# A7_POWER_-.net
KiCad netlist of a schematic drawn in Altium Designer
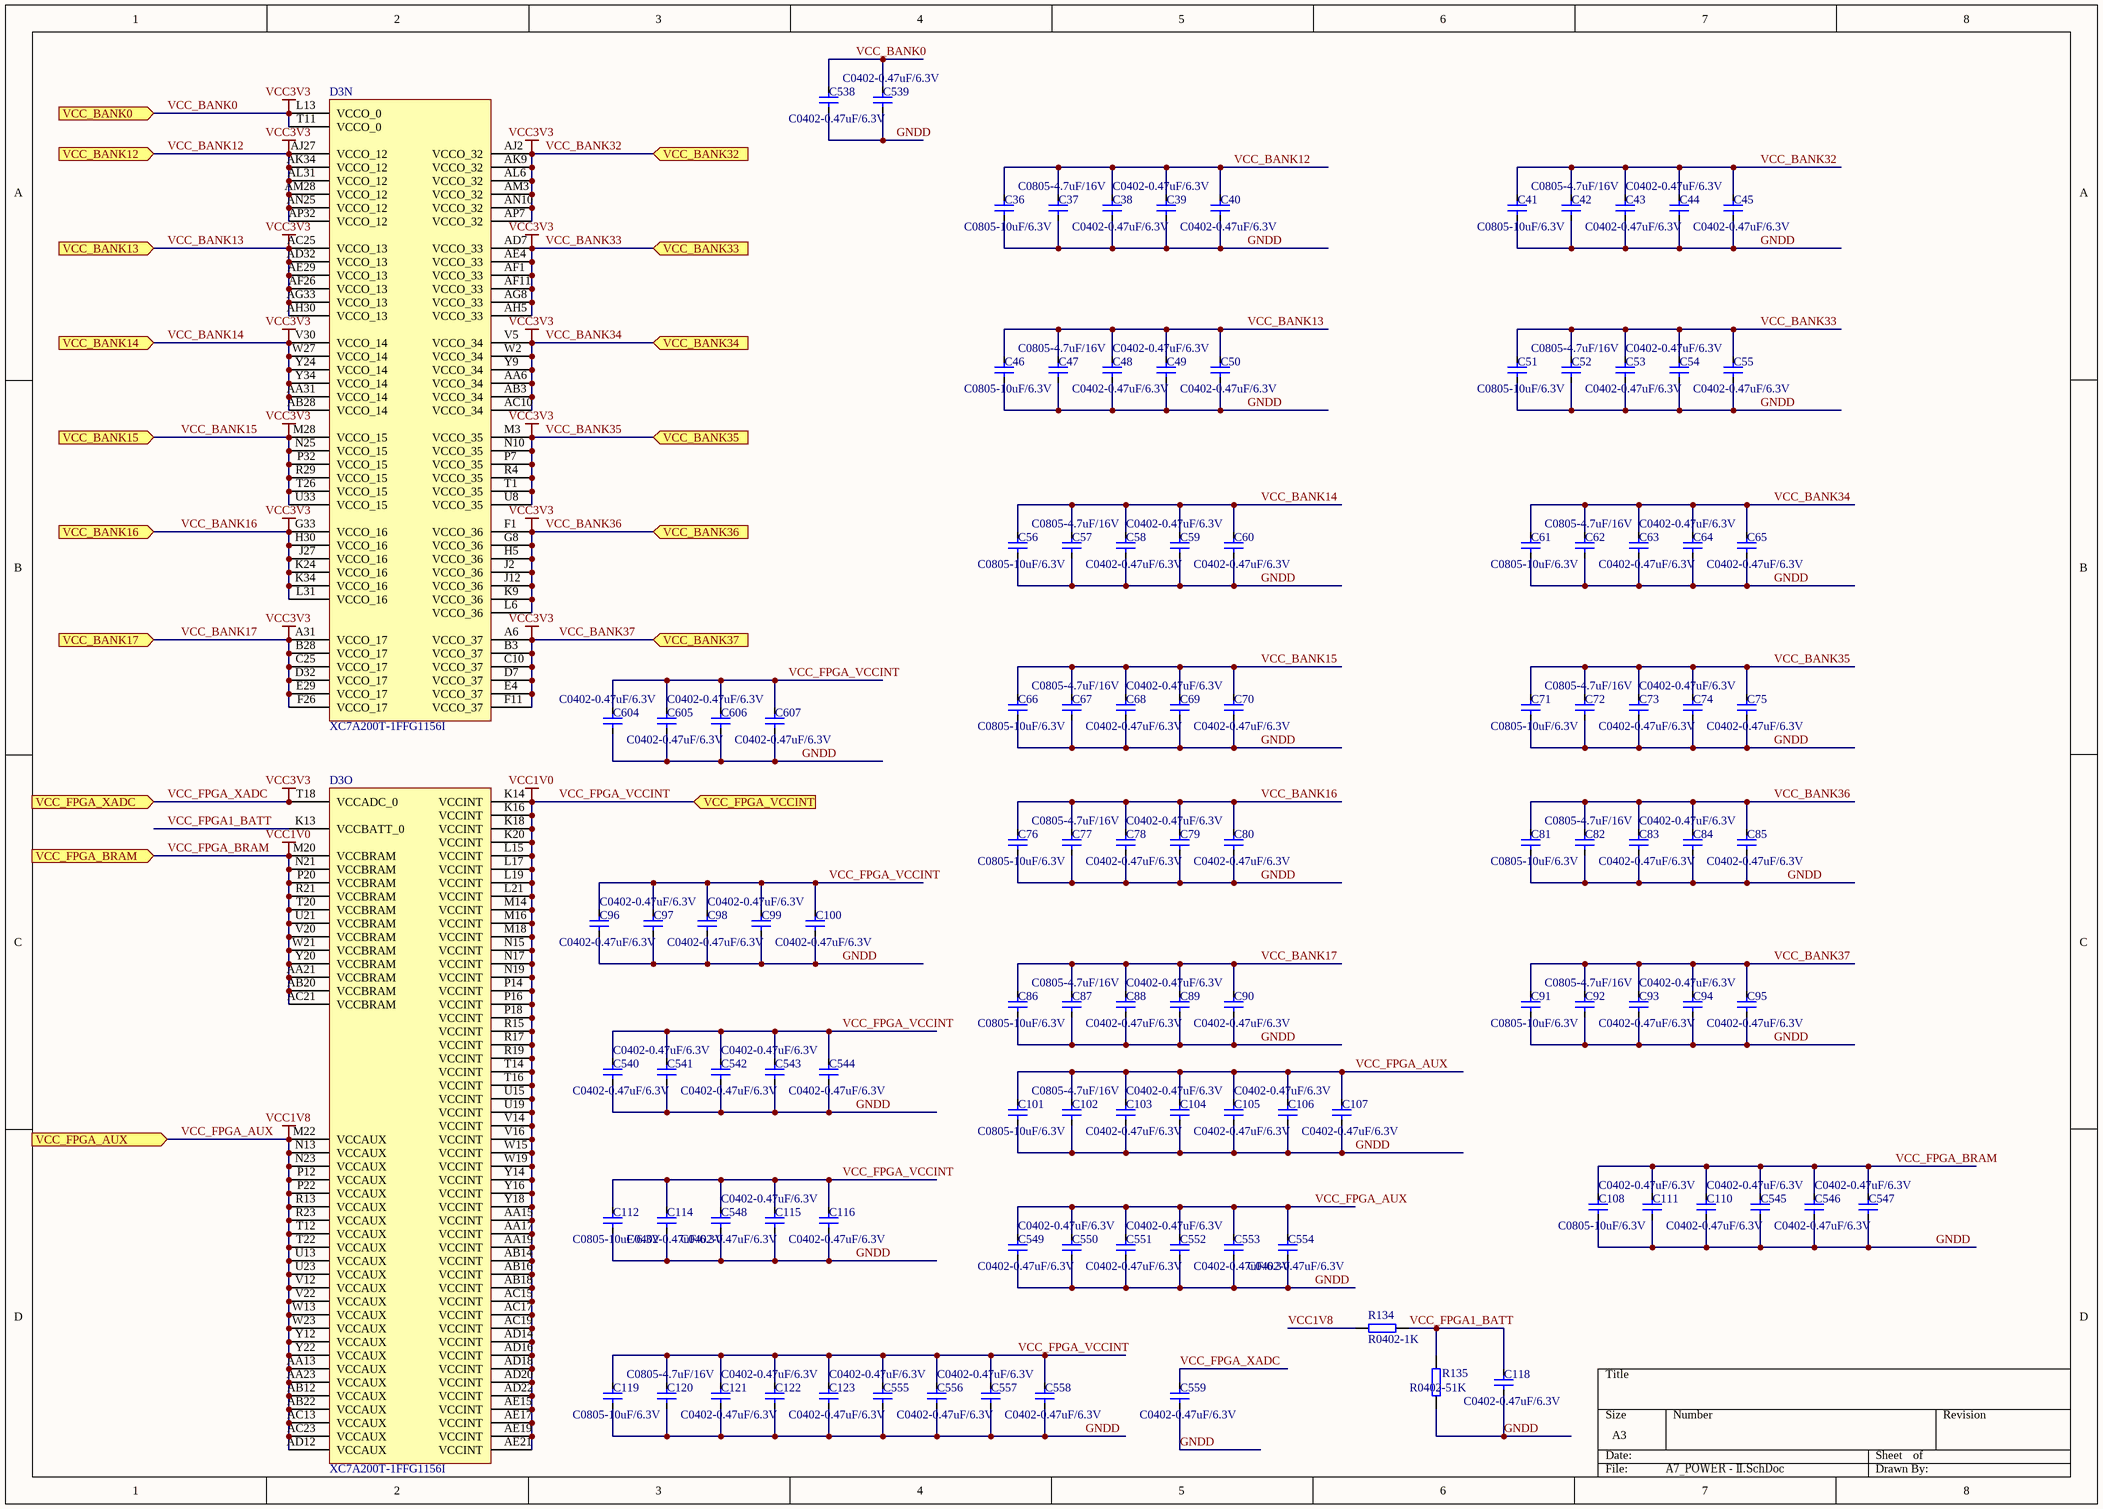
[diagram p0: A7_POWER - Ⅱ.SchDoc]

(export (version "E")
  (design (tool "Eeschema 10.0.6"))
  (components
    (comp (ref "C36")
      (value "C0805-10uF/6.3V")
      (footprint "C0805")
      (fields (field (name "SCHEMATIC_PART") "CAP"))
      (libsource (lib "Database_Libs1") (part "CAP"))
    )
    (comp (ref "C37")
      (value "C0805-4.7uF/16V")
      (footprint "C0805")
      (description "X7R")
      (fields (field (name "SCHEMATIC_PART") "CAP") (field (name "MANUFACTURER") "SAMSUNG"))
      (libsource (lib "Database_Libs1") (part "CAP"))
    )
    (comp (ref "C38")
      (value "C0402-0.47uF/6.3V")
      (footprint "C0402")
      (description "X7R")
      (fields (field (name "SCHEMATIC_PART") "CAP") (field (name "MANUFACTURER") "SAMSUNG"))
      (libsource (lib "Database_Libs1") (part "CAP"))
    )
    (comp (ref "C39")
      (value "C0402-0.47uF/6.3V")
      (footprint "C0402")
      (description "X7R")
      (fields (field (name "SCHEMATIC_PART") "CAP") (field (name "MANUFACTURER") "SAMSUNG"))
      (libsource (lib "Database_Libs1") (part "CAP"))
    )
    (comp (ref "C40")
      (value "C0402-0.47uF/6.3V")
      (footprint "C0402")
      (description "X7R")
      (fields (field (name "SCHEMATIC_PART") "CAP") (field (name "MANUFACTURER") "SAMSUNG"))
      (libsource (lib "Database_Libs1") (part "CAP"))
    )
    (comp (ref "C41")
      (value "C0805-10uF/6.3V")
      (footprint "C0805")
      (fields (field (name "SCHEMATIC_PART") "CAP"))
      (libsource (lib "Database_Libs1") (part "CAP"))
    )
    (comp (ref "C42")
      (value "C0805-4.7uF/16V")
      (footprint "C0805")
      (description "X7R")
      (fields (field (name "SCHEMATIC_PART") "CAP") (field (name "MANUFACTURER") "SAMSUNG"))
      (libsource (lib "Database_Libs1") (part "CAP"))
    )
    (comp (ref "C43")
      (value "C0402-0.47uF/6.3V")
      (footprint "C0402")
      (description "X7R")
      (fields (field (name "SCHEMATIC_PART") "CAP") (field (name "MANUFACTURER") "SAMSUNG"))
      (libsource (lib "Database_Libs1") (part "CAP"))
    )
    (comp (ref "C44")
      (value "C0402-0.47uF/6.3V")
      (footprint "C0402")
      (description "X7R")
      (fields (field (name "SCHEMATIC_PART") "CAP") (field (name "MANUFACTURER") "SAMSUNG"))
      (libsource (lib "Database_Libs1") (part "CAP"))
    )
    (comp (ref "C45")
      (value "C0402-0.47uF/6.3V")
      (footprint "C0402")
      (description "X7R")
      (fields (field (name "SCHEMATIC_PART") "CAP") (field (name "MANUFACTURER") "SAMSUNG"))
      (libsource (lib "Database_Libs1") (part "CAP"))
    )
    (comp (ref "C46")
      (value "C0805-10uF/6.3V")
      (footprint "C0805")
      (fields (field (name "SCHEMATIC_PART") "CAP"))
      (libsource (lib "Database_Libs1") (part "CAP"))
    )
    (comp (ref "C47")
      (value "C0805-4.7uF/16V")
      (footprint "C0805")
      (description "X7R")
      (fields (field (name "SCHEMATIC_PART") "CAP") (field (name "MANUFACTURER") "SAMSUNG"))
      (libsource (lib "Database_Libs1") (part "CAP"))
    )
    (comp (ref "C48")
      (value "C0402-0.47uF/6.3V")
      (footprint "C0402")
      (description "X7R")
      (fields (field (name "SCHEMATIC_PART") "CAP") (field (name "MANUFACTURER") "SAMSUNG"))
      (libsource (lib "Database_Libs1") (part "CAP"))
    )
    (comp (ref "C49")
      (value "C0402-0.47uF/6.3V")
      (footprint "C0402")
      (description "X7R")
      (fields (field (name "SCHEMATIC_PART") "CAP") (field (name "MANUFACTURER") "SAMSUNG"))
      (libsource (lib "Database_Libs1") (part "CAP"))
    )
    (comp (ref "C50")
      (value "C0402-0.47uF/6.3V")
      (footprint "C0402")
      (description "X7R")
      (fields (field (name "SCHEMATIC_PART") "CAP") (field (name "MANUFACTURER") "SAMSUNG"))
      (libsource (lib "Database_Libs1") (part "CAP"))
    )
    (comp (ref "C51")
      (value "C0805-10uF/6.3V")
      (footprint "C0805")
      (fields (field (name "SCHEMATIC_PART") "CAP"))
      (libsource (lib "Database_Libs1") (part "CAP"))
    )
    (comp (ref "C52")
      (value "C0805-4.7uF/16V")
      (footprint "C0805")
      (description "X7R")
      (fields (field (name "SCHEMATIC_PART") "CAP") (field (name "MANUFACTURER") "SAMSUNG"))
      (libsource (lib "Database_Libs1") (part "CAP"))
    )
    (comp (ref "C53")
      (value "C0402-0.47uF/6.3V")
      (footprint "C0402")
      (description "X7R")
      (fields (field (name "SCHEMATIC_PART") "CAP") (field (name "MANUFACTURER") "SAMSUNG"))
      (libsource (lib "Database_Libs1") (part "CAP"))
    )
    (comp (ref "C54")
      (value "C0402-0.47uF/6.3V")
      (footprint "C0402")
      (description "X7R")
      (fields (field (name "SCHEMATIC_PART") "CAP") (field (name "MANUFACTURER") "SAMSUNG"))
      (libsource (lib "Database_Libs1") (part "CAP"))
    )
    (comp (ref "C55")
      (value "C0402-0.47uF/6.3V")
      (footprint "C0402")
      (description "X7R")
      (fields (field (name "SCHEMATIC_PART") "CAP") (field (name "MANUFACTURER") "SAMSUNG"))
      (libsource (lib "Database_Libs1") (part "CAP"))
    )
    (comp (ref "C56")
      (value "C0805-10uF/6.3V")
      (footprint "C0805")
      (fields (field (name "SCHEMATIC_PART") "CAP"))
      (libsource (lib "Database_Libs1") (part "CAP"))
    )
    (comp (ref "C57")
      (value "C0805-4.7uF/16V")
      (footprint "C0805")
      (description "X7R")
      (fields (field (name "SCHEMATIC_PART") "CAP") (field (name "MANUFACTURER") "SAMSUNG"))
      (libsource (lib "Database_Libs1") (part "CAP"))
    )
    (comp (ref "C58")
      (value "C0402-0.47uF/6.3V")
      (footprint "C0402")
      (description "X7R")
      (fields (field (name "SCHEMATIC_PART") "CAP") (field (name "MANUFACTURER") "SAMSUNG"))
      (libsource (lib "Database_Libs1") (part "CAP"))
    )
    (comp (ref "C59")
      (value "C0402-0.47uF/6.3V")
      (footprint "C0402")
      (description "X7R")
      (fields (field (name "SCHEMATIC_PART") "CAP") (field (name "MANUFACTURER") "SAMSUNG"))
      (libsource (lib "Database_Libs1") (part "CAP"))
    )
    (comp (ref "C60")
      (value "C0402-0.47uF/6.3V")
      (footprint "C0402")
      (description "X7R")
      (fields (field (name "SCHEMATIC_PART") "CAP") (field (name "MANUFACTURER") "SAMSUNG"))
      (libsource (lib "Database_Libs1") (part "CAP"))
    )
    (comp (ref "C61")
      (value "C0805-10uF/6.3V")
      (footprint "C0805")
      (fields (field (name "SCHEMATIC_PART") "CAP"))
      (libsource (lib "Database_Libs1") (part "CAP"))
    )
    (comp (ref "C62")
      (value "C0805-4.7uF/16V")
      (footprint "C0805")
      (description "X7R")
      (fields (field (name "SCHEMATIC_PART") "CAP") (field (name "MANUFACTURER") "SAMSUNG"))
      (libsource (lib "Database_Libs1") (part "CAP"))
    )
    (comp (ref "C63")
      (value "C0402-0.47uF/6.3V")
      (footprint "C0402")
      (description "X7R")
      (fields (field (name "SCHEMATIC_PART") "CAP") (field (name "MANUFACTURER") "SAMSUNG"))
      (libsource (lib "Database_Libs1") (part "CAP"))
    )
    (comp (ref "C64")
      (value "C0402-0.47uF/6.3V")
      (footprint "C0402")
      (description "X7R")
      (fields (field (name "SCHEMATIC_PART") "CAP") (field (name "MANUFACTURER") "SAMSUNG"))
      (libsource (lib "Database_Libs1") (part "CAP"))
    )
    (comp (ref "C65")
      (value "C0402-0.47uF/6.3V")
      (footprint "C0402")
      (description "X7R")
      (fields (field (name "SCHEMATIC_PART") "CAP") (field (name "MANUFACTURER") "SAMSUNG"))
      (libsource (lib "Database_Libs1") (part "CAP"))
    )
    (comp (ref "C66")
      (value "C0805-10uF/6.3V")
      (footprint "C0805")
      (fields (field (name "SCHEMATIC_PART") "CAP"))
      (libsource (lib "Database_Libs1") (part "CAP"))
    )
    (comp (ref "C67")
      (value "C0805-4.7uF/16V")
      (footprint "C0805")
      (description "X7R")
      (fields (field (name "SCHEMATIC_PART") "CAP") (field (name "MANUFACTURER") "SAMSUNG"))
      (libsource (lib "Database_Libs1") (part "CAP"))
    )
    (comp (ref "C68")
      (value "C0402-0.47uF/6.3V")
      (footprint "C0402")
      (description "X7R")
      (fields (field (name "SCHEMATIC_PART") "CAP") (field (name "MANUFACTURER") "SAMSUNG"))
      (libsource (lib "Database_Libs1") (part "CAP"))
    )
    (comp (ref "C69")
      (value "C0402-0.47uF/6.3V")
      (footprint "C0402")
      (description "X7R")
      (fields (field (name "SCHEMATIC_PART") "CAP") (field (name "MANUFACTURER") "SAMSUNG"))
      (libsource (lib "Database_Libs1") (part "CAP"))
    )
    (comp (ref "C70")
      (value "C0402-0.47uF/6.3V")
      (footprint "C0402")
      (description "X7R")
      (fields (field (name "SCHEMATIC_PART") "CAP") (field (name "MANUFACTURER") "SAMSUNG"))
      (libsource (lib "Database_Libs1") (part "CAP"))
    )
    (comp (ref "C71")
      (value "C0805-10uF/6.3V")
      (footprint "C0805")
      (fields (field (name "SCHEMATIC_PART") "CAP"))
      (libsource (lib "Database_Libs1") (part "CAP"))
    )
    (comp (ref "C72")
      (value "C0805-4.7uF/16V")
      (footprint "C0805")
      (description "X7R")
      (fields (field (name "SCHEMATIC_PART") "CAP") (field (name "MANUFACTURER") "SAMSUNG"))
      (libsource (lib "Database_Libs1") (part "CAP"))
    )
    (comp (ref "C73")
      (value "C0402-0.47uF/6.3V")
      (footprint "C0402")
      (description "X7R")
      (fields (field (name "SCHEMATIC_PART") "CAP") (field (name "MANUFACTURER") "SAMSUNG"))
      (libsource (lib "Database_Libs1") (part "CAP"))
    )
    (comp (ref "C74")
      (value "C0402-0.47uF/6.3V")
      (footprint "C0402")
      (description "X7R")
      (fields (field (name "SCHEMATIC_PART") "CAP") (field (name "MANUFACTURER") "SAMSUNG"))
      (libsource (lib "Database_Libs1") (part "CAP"))
    )
    (comp (ref "C75")
      (value "C0402-0.47uF/6.3V")
      (footprint "C0402")
      (description "X7R")
      (fields (field (name "SCHEMATIC_PART") "CAP") (field (name "MANUFACTURER") "SAMSUNG"))
      (libsource (lib "Database_Libs1") (part "CAP"))
    )
    (comp (ref "C76")
      (value "C0805-10uF/6.3V")
      (footprint "C0805")
      (fields (field (name "SCHEMATIC_PART") "CAP"))
      (libsource (lib "Database_Libs1") (part "CAP"))
    )
    (comp (ref "C77")
      (value "C0805-4.7uF/16V")
      (footprint "C0805")
      (description "X7R")
      (fields (field (name "SCHEMATIC_PART") "CAP") (field (name "MANUFACTURER") "SAMSUNG"))
      (libsource (lib "Database_Libs1") (part "CAP"))
    )
    (comp (ref "C78")
      (value "C0402-0.47uF/6.3V")
      (footprint "C0402")
      (description "X7R")
      (fields (field (name "SCHEMATIC_PART") "CAP") (field (name "MANUFACTURER") "SAMSUNG"))
      (libsource (lib "Database_Libs1") (part "CAP"))
    )
    (comp (ref "C79")
      (value "C0402-0.47uF/6.3V")
      (footprint "C0402")
      (description "X7R")
      (fields (field (name "SCHEMATIC_PART") "CAP") (field (name "MANUFACTURER") "SAMSUNG"))
      (libsource (lib "Database_Libs1") (part "CAP"))
    )
    (comp (ref "C80")
      (value "C0402-0.47uF/6.3V")
      (footprint "C0402")
      (description "X7R")
      (fields (field (name "SCHEMATIC_PART") "CAP") (field (name "MANUFACTURER") "SAMSUNG"))
      (libsource (lib "Database_Libs1") (part "CAP"))
    )
    (comp (ref "C81")
      (value "C0805-10uF/6.3V")
      (footprint "C0805")
      (fields (field (name "SCHEMATIC_PART") "CAP"))
      (libsource (lib "Database_Libs1") (part "CAP"))
    )
    (comp (ref "C82")
      (value "C0805-4.7uF/16V")
      (footprint "C0805")
      (description "X7R")
      (fields (field (name "SCHEMATIC_PART") "CAP") (field (name "MANUFACTURER") "SAMSUNG"))
      (libsource (lib "Database_Libs1") (part "CAP"))
    )
    (comp (ref "C83")
      (value "C0402-0.47uF/6.3V")
      (footprint "C0402")
      (description "X7R")
      (fields (field (name "SCHEMATIC_PART") "CAP") (field (name "MANUFACTURER") "SAMSUNG"))
      (libsource (lib "Database_Libs1") (part "CAP"))
    )
    (comp (ref "C84")
      (value "C0402-0.47uF/6.3V")
      (footprint "C0402")
      (description "X7R")
      (fields (field (name "SCHEMATIC_PART") "CAP") (field (name "MANUFACTURER") "SAMSUNG"))
      (libsource (lib "Database_Libs1") (part "CAP"))
    )
    (comp (ref "C85")
      (value "C0402-0.47uF/6.3V")
      (footprint "C0402")
      (description "X7R")
      (fields (field (name "SCHEMATIC_PART") "CAP") (field (name "MANUFACTURER") "SAMSUNG"))
      (libsource (lib "Database_Libs1") (part "CAP"))
    )
    (comp (ref "C86")
      (value "C0805-10uF/6.3V")
      (footprint "C0805")
      (fields (field (name "SCHEMATIC_PART") "CAP"))
      (libsource (lib "Database_Libs1") (part "CAP"))
    )
    (comp (ref "C87")
      (value "C0805-4.7uF/16V")
      (footprint "C0805")
      (description "X7R")
      (fields (field (name "SCHEMATIC_PART") "CAP") (field (name "MANUFACTURER") "SAMSUNG"))
      (libsource (lib "Database_Libs1") (part "CAP"))
    )
    (comp (ref "C88")
      (value "C0402-0.47uF/6.3V")
      (footprint "C0402")
      (description "X7R")
      (fields (field (name "SCHEMATIC_PART") "CAP") (field (name "MANUFACTURER") "SAMSUNG"))
      (libsource (lib "Database_Libs1") (part "CAP"))
    )
    (comp (ref "C89")
      (value "C0402-0.47uF/6.3V")
      (footprint "C0402")
      (description "X7R")
      (fields (field (name "SCHEMATIC_PART") "CAP") (field (name "MANUFACTURER") "SAMSUNG"))
      (libsource (lib "Database_Libs1") (part "CAP"))
    )
    (comp (ref "C90")
      (value "C0402-0.47uF/6.3V")
      (footprint "C0402")
      (description "X7R")
      (fields (field (name "SCHEMATIC_PART") "CAP") (field (name "MANUFACTURER") "SAMSUNG"))
      (libsource (lib "Database_Libs1") (part "CAP"))
    )
    (comp (ref "C91")
      (value "C0805-10uF/6.3V")
      (footprint "C0805")
      (fields (field (name "SCHEMATIC_PART") "CAP"))
      (libsource (lib "Database_Libs1") (part "CAP"))
    )
    (comp (ref "C92")
      (value "C0805-4.7uF/16V")
      (footprint "C0805")
      (description "X7R")
      (fields (field (name "SCHEMATIC_PART") "CAP") (field (name "MANUFACTURER") "SAMSUNG"))
      (libsource (lib "Database_Libs1") (part "CAP"))
    )
    (comp (ref "C93")
      (value "C0402-0.47uF/6.3V")
      (footprint "C0402")
      (description "X7R")
      (fields (field (name "SCHEMATIC_PART") "CAP") (field (name "MANUFACTURER") "SAMSUNG"))
      (libsource (lib "Database_Libs1") (part "CAP"))
    )
    (comp (ref "C94")
      (value "C0402-0.47uF/6.3V")
      (footprint "C0402")
      (description "X7R")
      (fields (field (name "SCHEMATIC_PART") "CAP") (field (name "MANUFACTURER") "SAMSUNG"))
      (libsource (lib "Database_Libs1") (part "CAP"))
    )
    (comp (ref "C95")
      (value "C0402-0.47uF/6.3V")
      (footprint "C0402")
      (description "X7R")
      (fields (field (name "SCHEMATIC_PART") "CAP") (field (name "MANUFACTURER") "SAMSUNG"))
      (libsource (lib "Database_Libs1") (part "CAP"))
    )
    (comp (ref "C96")
      (value "C0402-0.47uF/6.3V")
      (footprint "C0402")
      (description "X7R")
      (fields (field (name "SCHEMATIC_PART") "CAP") (field (name "MANUFACTURER") "SAMSUNG"))
      (libsource (lib "Database_Libs1") (part "CAP"))
    )
    (comp (ref "C97")
      (value "C0402-0.47uF/6.3V")
      (footprint "C0402")
      (description "X7R")
      (fields (field (name "SCHEMATIC_PART") "CAP") (field (name "MANUFACTURER") "SAMSUNG"))
      (libsource (lib "Database_Libs1") (part "CAP"))
    )
    (comp (ref "C98")
      (value "C0402-0.47uF/6.3V")
      (footprint "C0402")
      (description "X7R")
      (fields (field (name "SCHEMATIC_PART") "CAP") (field (name "MANUFACTURER") "SAMSUNG"))
      (libsource (lib "Database_Libs1") (part "CAP"))
    )
    (comp (ref "C99")
      (value "C0402-0.47uF/6.3V")
      (footprint "C0402")
      (description "X7R")
      (fields (field (name "SCHEMATIC_PART") "CAP") (field (name "MANUFACTURER") "SAMSUNG"))
      (libsource (lib "Database_Libs1") (part "CAP"))
    )
    (comp (ref "C100")
      (value "C0402-0.47uF/6.3V")
      (footprint "C0402")
      (description "X7R")
      (fields (field (name "SCHEMATIC_PART") "CAP") (field (name "MANUFACTURER") "SAMSUNG"))
      (libsource (lib "Database_Libs1") (part "CAP"))
    )
    (comp (ref "C101")
      (value "C0805-10uF/6.3V")
      (footprint "C0805")
      (fields (field (name "SCHEMATIC_PART") "CAP"))
      (libsource (lib "Database_Libs1") (part "CAP"))
    )
    (comp (ref "C102")
      (value "C0805-4.7uF/16V")
      (footprint "C0805")
      (description "X7R")
      (fields (field (name "SCHEMATIC_PART") "CAP") (field (name "MANUFACTURER") "SAMSUNG"))
      (libsource (lib "Database_Libs1") (part "CAP"))
    )
    (comp (ref "C103")
      (value "C0402-0.47uF/6.3V")
      (footprint "C0402")
      (description "X7R")
      (fields (field (name "SCHEMATIC_PART") "CAP") (field (name "MANUFACTURER") "SAMSUNG"))
      (libsource (lib "Database_Libs1") (part "CAP"))
    )
    (comp (ref "C104")
      (value "C0402-0.47uF/6.3V")
      (footprint "C0402")
      (description "X7R")
      (fields (field (name "SCHEMATIC_PART") "CAP") (field (name "MANUFACTURER") "SAMSUNG"))
      (libsource (lib "Database_Libs1") (part "CAP"))
    )
    (comp (ref "C105")
      (value "C0402-0.47uF/6.3V")
      (footprint "C0402")
      (description "X7R")
      (fields (field (name "SCHEMATIC_PART") "CAP") (field (name "MANUFACTURER") "SAMSUNG"))
      (libsource (lib "Database_Libs1") (part "CAP"))
    )
    (comp (ref "C106")
      (value "C0402-0.47uF/6.3V")
      (footprint "C0402")
      (description "X7R")
      (fields (field (name "SCHEMATIC_PART") "CAP") (field (name "MANUFACTURER") "SAMSUNG"))
      (libsource (lib "Database_Libs1") (part "CAP"))
    )
    (comp (ref "C107")
      (value "C0402-0.47uF/6.3V")
      (footprint "C0402")
      (description "X7R")
      (fields (field (name "SCHEMATIC_PART") "CAP") (field (name "MANUFACTURER") "SAMSUNG"))
      (libsource (lib "Database_Libs1") (part "CAP"))
    )
    (comp (ref "C108")
      (value "C0805-10uF/6.3V")
      (footprint "C0805")
      (fields (field (name "SCHEMATIC_PART") "CAP"))
      (libsource (lib "Database_Libs1") (part "CAP"))
    )
    (comp (ref "C110")
      (value "C0402-0.47uF/6.3V")
      (footprint "C0402")
      (description "X7R")
      (fields (field (name "SCHEMATIC_PART") "CAP") (field (name "MANUFACTURER") "SAMSUNG"))
      (libsource (lib "Database_Libs1") (part "CAP"))
    )
    (comp (ref "C111")
      (value "C0402-0.47uF/6.3V")
      (footprint "C0402")
      (description "X7R")
      (fields (field (name "SCHEMATIC_PART") "CAP") (field (name "MANUFACTURER") "SAMSUNG"))
      (libsource (lib "Database_Libs1") (part "CAP"))
    )
    (comp (ref "C112")
      (value "C0805-10uF/6.3V")
      (footprint "C0805")
      (fields (field (name "SCHEMATIC_PART") "CAP"))
      (libsource (lib "Database_Libs1") (part "CAP"))
    )
    (comp (ref "C114")
      (value "C0402-0.47uF/6.3V")
      (footprint "C0402")
      (description "X7R")
      (fields (field (name "SCHEMATIC_PART") "CAP") (field (name "MANUFACTURER") "SAMSUNG"))
      (libsource (lib "Database_Libs1") (part "CAP"))
    )
    (comp (ref "C115")
      (value "C0402-0.47uF/6.3V")
      (footprint "C0402")
      (description "X7R")
      (fields (field (name "SCHEMATIC_PART") "CAP") (field (name "MANUFACTURER") "SAMSUNG"))
      (libsource (lib "Database_Libs1") (part "CAP"))
    )
    (comp (ref "C116")
      (value "C0402-0.47uF/6.3V")
      (footprint "C0402")
      (description "X7R")
      (fields (field (name "SCHEMATIC_PART") "CAP") (field (name "MANUFACTURER") "SAMSUNG"))
      (libsource (lib "Database_Libs1") (part "CAP"))
    )
    (comp (ref "C118")
      (value "C0402-0.47uF/6.3V")
      (footprint "C0402")
      (description "X7R")
      (fields (field (name "SCHEMATIC_PART") "CAP") (field (name "MANUFACTURER") "SAMSUNG"))
      (libsource (lib "Database_Libs1") (part "CAP"))
    )
    (comp (ref "C119")
      (value "C0805-10uF/6.3V")
      (footprint "C0805")
      (fields (field (name "SCHEMATIC_PART") "CAP"))
      (libsource (lib "Database_Libs1") (part "CAP"))
    )
    (comp (ref "C120")
      (value "C0805-4.7uF/16V")
      (footprint "C0805")
      (description "X7R")
      (fields (field (name "SCHEMATIC_PART") "CAP") (field (name "MANUFACTURER") "SAMSUNG"))
      (libsource (lib "Database_Libs1") (part "CAP"))
    )
    (comp (ref "C121")
      (value "C0402-0.47uF/6.3V")
      (footprint "C0402")
      (description "X7R")
      (fields (field (name "SCHEMATIC_PART") "CAP") (field (name "MANUFACTURER") "SAMSUNG"))
      (libsource (lib "Database_Libs1") (part "CAP"))
    )
    (comp (ref "C122")
      (value "C0402-0.47uF/6.3V")
      (footprint "C0402")
      (description "X7R")
      (fields (field (name "SCHEMATIC_PART") "CAP") (field (name "MANUFACTURER") "SAMSUNG"))
      (libsource (lib "Database_Libs1") (part "CAP"))
    )
    (comp (ref "C123")
      (value "C0402-0.47uF/6.3V")
      (footprint "C0402")
      (description "X7R")
      (fields (field (name "SCHEMATIC_PART") "CAP") (field (name "MANUFACTURER") "SAMSUNG"))
      (libsource (lib "Database_Libs1") (part "CAP"))
    )
    (comp (ref "C538")
      (value "C0402-0.47uF/6.3V")
      (footprint "C0402")
      (description "X7R")
      (fields (field (name "SCHEMATIC_PART") "CAP") (field (name "MANUFACTURER") "SAMSUNG"))
      (libsource (lib "Database_Libs1") (part "CAP"))
    )
    (comp (ref "C539")
      (value "C0402-0.47uF/6.3V")
      (footprint "C0402")
      (description "X7R")
      (fields (field (name "SCHEMATIC_PART") "CAP") (field (name "MANUFACTURER") "SAMSUNG"))
      (libsource (lib "Database_Libs1") (part "CAP"))
    )
    (comp (ref "C540")
      (value "C0402-0.47uF/6.3V")
      (footprint "C0402")
      (description "X7R")
      (fields (field (name "SCHEMATIC_PART") "CAP") (field (name "MANUFACTURER") "SAMSUNG"))
      (libsource (lib "Database_Libs1") (part "CAP"))
    )
    (comp (ref "C541")
      (value "C0402-0.47uF/6.3V")
      (footprint "C0402")
      (description "X7R")
      (fields (field (name "SCHEMATIC_PART") "CAP") (field (name "MANUFACTURER") "SAMSUNG"))
      (libsource (lib "Database_Libs1") (part "CAP"))
    )
    (comp (ref "C542")
      (value "C0402-0.47uF/6.3V")
      (footprint "C0402")
      (description "X7R")
      (fields (field (name "SCHEMATIC_PART") "CAP") (field (name "MANUFACTURER") "SAMSUNG"))
      (libsource (lib "Database_Libs1") (part "CAP"))
    )
    (comp (ref "C543")
      (value "C0402-0.47uF/6.3V")
      (footprint "C0402")
      (description "X7R")
      (fields (field (name "SCHEMATIC_PART") "CAP") (field (name "MANUFACTURER") "SAMSUNG"))
      (libsource (lib "Database_Libs1") (part "CAP"))
    )
    (comp (ref "C544")
      (value "C0402-0.47uF/6.3V")
      (footprint "C0402")
      (description "X7R")
      (fields (field (name "SCHEMATIC_PART") "CAP") (field (name "MANUFACTURER") "SAMSUNG"))
      (libsource (lib "Database_Libs1") (part "CAP"))
    )
    (comp (ref "C545")
      (value "C0402-0.47uF/6.3V")
      (footprint "C0402")
      (description "X7R")
      (fields (field (name "SCHEMATIC_PART") "CAP") (field (name "MANUFACTURER") "SAMSUNG"))
      (libsource (lib "Database_Libs1") (part "CAP"))
    )
    (comp (ref "C546")
      (value "C0402-0.47uF/6.3V")
      (footprint "C0402")
      (description "X7R")
      (fields (field (name "SCHEMATIC_PART") "CAP") (field (name "MANUFACTURER") "SAMSUNG"))
      (libsource (lib "Database_Libs1") (part "CAP"))
    )
    (comp (ref "C547")
      (value "C0402-0.47uF/6.3V")
      (footprint "C0402")
      (description "X7R")
      (fields (field (name "SCHEMATIC_PART") "CAP") (field (name "MANUFACTURER") "SAMSUNG"))
      (libsource (lib "Database_Libs1") (part "CAP"))
    )
    (comp (ref "C548")
      (value "C0402-0.47uF/6.3V")
      (footprint "C0402")
      (description "X7R")
      (fields (field (name "SCHEMATIC_PART") "CAP") (field (name "MANUFACTURER") "SAMSUNG"))
      (libsource (lib "Database_Libs1") (part "CAP"))
    )
    (comp (ref "C549")
      (value "C0402-0.47uF/6.3V")
      (footprint "C0402")
      (description "X7R")
      (fields (field (name "SCHEMATIC_PART") "CAP") (field (name "MANUFACTURER") "SAMSUNG"))
      (libsource (lib "Database_Libs1") (part "CAP"))
    )
    (comp (ref "C550")
      (value "C0402-0.47uF/6.3V")
      (footprint "C0402")
      (description "X7R")
      (fields (field (name "SCHEMATIC_PART") "CAP") (field (name "MANUFACTURER") "SAMSUNG"))
      (libsource (lib "Database_Libs1") (part "CAP"))
    )
    (comp (ref "C551")
      (value "C0402-0.47uF/6.3V")
      (footprint "C0402")
      (description "X7R")
      (fields (field (name "SCHEMATIC_PART") "CAP") (field (name "MANUFACTURER") "SAMSUNG"))
      (libsource (lib "Database_Libs1") (part "CAP"))
    )
    (comp (ref "C552")
      (value "C0402-0.47uF/6.3V")
      (footprint "C0402")
      (description "X7R")
      (fields (field (name "SCHEMATIC_PART") "CAP") (field (name "MANUFACTURER") "SAMSUNG"))
      (libsource (lib "Database_Libs1") (part "CAP"))
    )
    (comp (ref "C553")
      (value "C0402-0.47uF/6.3V")
      (footprint "C0402")
      (description "X7R")
      (fields (field (name "SCHEMATIC_PART") "CAP") (field (name "MANUFACTURER") "SAMSUNG"))
      (libsource (lib "Database_Libs1") (part "CAP"))
    )
    (comp (ref "C554")
      (value "C0402-0.47uF/6.3V")
      (footprint "C0402")
      (description "X7R")
      (fields (field (name "SCHEMATIC_PART") "CAP") (field (name "MANUFACTURER") "SAMSUNG"))
      (libsource (lib "Database_Libs1") (part "CAP"))
    )
    (comp (ref "C555")
      (value "C0402-0.47uF/6.3V")
      (footprint "C0402")
      (description "X7R")
      (fields (field (name "SCHEMATIC_PART") "CAP") (field (name "MANUFACTURER") "SAMSUNG"))
      (libsource (lib "Database_Libs1") (part "CAP"))
    )
    (comp (ref "C556")
      (value "C0402-0.47uF/6.3V")
      (footprint "C0402")
      (description "X7R")
      (fields (field (name "SCHEMATIC_PART") "CAP") (field (name "MANUFACTURER") "SAMSUNG"))
      (libsource (lib "Database_Libs1") (part "CAP"))
    )
    (comp (ref "C557")
      (value "C0402-0.47uF/6.3V")
      (footprint "C0402")
      (description "X7R")
      (fields (field (name "SCHEMATIC_PART") "CAP") (field (name "MANUFACTURER") "SAMSUNG"))
      (libsource (lib "Database_Libs1") (part "CAP"))
    )
    (comp (ref "C558")
      (value "C0402-0.47uF/6.3V")
      (footprint "C0402")
      (description "X7R")
      (fields (field (name "SCHEMATIC_PART") "CAP") (field (name "MANUFACTURER") "SAMSUNG"))
      (libsource (lib "Database_Libs1") (part "CAP"))
    )
    (comp (ref "C559")
      (value "C0402-0.47uF/6.3V")
      (footprint "C0402")
      (description "X7R")
      (fields (field (name "SCHEMATIC_PART") "CAP") (field (name "MANUFACTURER") "SAMSUNG"))
      (libsource (lib "Database_Libs1") (part "CAP"))
    )
    (comp (ref "C604")
      (value "C0402-0.47uF/6.3V")
      (footprint "C0402")
      (description "X7R")
      (fields (field (name "SCHEMATIC_PART") "CAP") (field (name "MANUFACTURER") "SAMSUNG"))
      (libsource (lib "Database_Libs1") (part "CAP"))
    )
    (comp (ref "C605")
      (value "C0402-0.47uF/6.3V")
      (footprint "C0402")
      (description "X7R")
      (fields (field (name "SCHEMATIC_PART") "CAP") (field (name "MANUFACTURER") "SAMSUNG"))
      (libsource (lib "Database_Libs1") (part "CAP"))
    )
    (comp (ref "C606")
      (value "C0402-0.47uF/6.3V")
      (footprint "C0402")
      (description "X7R")
      (fields (field (name "SCHEMATIC_PART") "CAP") (field (name "MANUFACTURER") "SAMSUNG"))
      (libsource (lib "Database_Libs1") (part "CAP"))
    )
    (comp (ref "C607")
      (value "C0402-0.47uF/6.3V")
      (footprint "C0402")
      (description "X7R")
      (fields (field (name "SCHEMATIC_PART") "CAP") (field (name "MANUFACTURER") "SAMSUNG"))
      (libsource (lib "Database_Libs1") (part "CAP"))
    )
    (comp (ref "D3")
      (value "XC7A200T-1FFG1156I")
      (footprint "FFG1156")
      (description "Artix-7 FPGA, 500 User I/Os, 16 GTP, 1156-Ball BGA, Speed Grade 1, Industrial Grade, Pb-Free")
      (fields (field (name "GENERIC PART NUMBER") "XC7A200T") (field (name "MANUFACTURER") "Xilinx"))
      (libsource (lib "Xilinx Artix-7") (part "XC7A200T-1FFG1156I"))
    )
    (comp (ref "R134")
      (value "R0402-1K")
      (footprint "R0402")
      (fields (field (name "SCHEMATIC_PART") "RES") (field (name "MANUFACTURER") "SAMSUNG"))
      (libsource (lib "Database_Libs1") (part "RES"))
    )
    (comp (ref "R135")
      (value "R0402-51K")
      (footprint "R0402")
      (fields (field (name "SCHEMATIC_PART") "RES") (field (name "MANUFACTURER") "SAMSUNG"))
      (libsource (lib "Database_Libs1") (part "RES"))
    )
  )
  (nets
    (net (code "1") (name "/GNDD") (class "Default")
      (node (ref "C100") (pin "2") (pinfunction "2_2") (pintype "passive"))
      (node (ref "C101") (pin "2") (pinfunction "2_2") (pintype "passive"))
      (node (ref "C102") (pin "2") (pinfunction "2_2") (pintype "passive"))
      (node (ref "C103") (pin "2") (pinfunction "2_2") (pintype "passive"))
      (node (ref "C104") (pin "2") (pinfunction "2_2") (pintype "passive"))
      (node (ref "C105") (pin "2") (pinfunction "2_2") (pintype "passive"))
      (node (ref "C106") (pin "2") (pinfunction "2_2") (pintype "passive"))
      (node (ref "C107") (pin "2") (pinfunction "2_2") (pintype "passive"))
      (node (ref "C108") (pin "2") (pinfunction "2_2") (pintype "passive"))
      (node (ref "C110") (pin "2") (pinfunction "2_2") (pintype "passive"))
      (node (ref "C111") (pin "2") (pinfunction "2_2") (pintype "passive"))
      (node (ref "C112") (pin "2") (pinfunction "2_2") (pintype "passive"))
      (node (ref "C114") (pin "2") (pinfunction "2_2") (pintype "passive"))
      (node (ref "C115") (pin "2") (pinfunction "2_2") (pintype "passive"))
      (node (ref "C116") (pin "2") (pinfunction "2_2") (pintype "passive"))
      (node (ref "C118") (pin "2") (pinfunction "2_2") (pintype "passive"))
      (node (ref "C119") (pin "2") (pinfunction "2_2") (pintype "passive"))
      (node (ref "C120") (pin "2") (pinfunction "2_2") (pintype "passive"))
      (node (ref "C121") (pin "2") (pinfunction "2_2") (pintype "passive"))
      (node (ref "C122") (pin "2") (pinfunction "2_2") (pintype "passive"))
      (node (ref "C123") (pin "2") (pinfunction "2_2") (pintype "passive"))
      (node (ref "C36") (pin "2") (pinfunction "2_2") (pintype "passive"))
      (node (ref "C37") (pin "2") (pinfunction "2_2") (pintype "passive"))
      (node (ref "C38") (pin "2") (pinfunction "2_2") (pintype "passive"))
      (node (ref "C39") (pin "2") (pinfunction "2_2") (pintype "passive"))
      (node (ref "C40") (pin "2") (pinfunction "2_2") (pintype "passive"))
      (node (ref "C41") (pin "2") (pinfunction "2_2") (pintype "passive"))
      (node (ref "C42") (pin "2") (pinfunction "2_2") (pintype "passive"))
      (node (ref "C43") (pin "2") (pinfunction "2_2") (pintype "passive"))
      (node (ref "C44") (pin "2") (pinfunction "2_2") (pintype "passive"))
      (node (ref "C45") (pin "2") (pinfunction "2_2") (pintype "passive"))
      (node (ref "C46") (pin "2") (pinfunction "2_2") (pintype "passive"))
      (node (ref "C47") (pin "2") (pinfunction "2_2") (pintype "passive"))
      (node (ref "C48") (pin "2") (pinfunction "2_2") (pintype "passive"))
      (node (ref "C49") (pin "2") (pinfunction "2_2") (pintype "passive"))
      (node (ref "C50") (pin "2") (pinfunction "2_2") (pintype "passive"))
      (node (ref "C51") (pin "2") (pinfunction "2_2") (pintype "passive"))
      (node (ref "C52") (pin "2") (pinfunction "2_2") (pintype "passive"))
      (node (ref "C53") (pin "2") (pinfunction "2_2") (pintype "passive"))
      (node (ref "C538") (pin "2") (pinfunction "2_2") (pintype "passive"))
      (node (ref "C539") (pin "2") (pinfunction "2_2") (pintype "passive"))
      (node (ref "C54") (pin "2") (pinfunction "2_2") (pintype "passive"))
      (node (ref "C540") (pin "2") (pinfunction "2_2") (pintype "passive"))
      (node (ref "C541") (pin "2") (pinfunction "2_2") (pintype "passive"))
      (node (ref "C542") (pin "2") (pinfunction "2_2") (pintype "passive"))
      (node (ref "C543") (pin "2") (pinfunction "2_2") (pintype "passive"))
      (node (ref "C544") (pin "2") (pinfunction "2_2") (pintype "passive"))
      (node (ref "C545") (pin "2") (pinfunction "2_2") (pintype "passive"))
      (node (ref "C546") (pin "2") (pinfunction "2_2") (pintype "passive"))
      (node (ref "C547") (pin "2") (pinfunction "2_2") (pintype "passive"))
      (node (ref "C548") (pin "2") (pinfunction "2_2") (pintype "passive"))
      (node (ref "C549") (pin "2") (pinfunction "2_2") (pintype "passive"))
      (node (ref "C55") (pin "2") (pinfunction "2_2") (pintype "passive"))
      (node (ref "C550") (pin "2") (pinfunction "2_2") (pintype "passive"))
      (node (ref "C551") (pin "2") (pinfunction "2_2") (pintype "passive"))
      (node (ref "C552") (pin "2") (pinfunction "2_2") (pintype "passive"))
      (node (ref "C553") (pin "2") (pinfunction "2_2") (pintype "passive"))
      (node (ref "C554") (pin "2") (pinfunction "2_2") (pintype "passive"))
      (node (ref "C555") (pin "2") (pinfunction "2_2") (pintype "passive"))
      (node (ref "C556") (pin "2") (pinfunction "2_2") (pintype "passive"))
      (node (ref "C557") (pin "2") (pinfunction "2_2") (pintype "passive"))
      (node (ref "C558") (pin "2") (pinfunction "2_2") (pintype "passive"))
      (node (ref "C559") (pin "2") (pinfunction "2_2") (pintype "passive"))
      (node (ref "C56") (pin "2") (pinfunction "2_2") (pintype "passive"))
      (node (ref "C57") (pin "2") (pinfunction "2_2") (pintype "passive"))
      (node (ref "C58") (pin "2") (pinfunction "2_2") (pintype "passive"))
      (node (ref "C59") (pin "2") (pinfunction "2_2") (pintype "passive"))
      (node (ref "C60") (pin "2") (pinfunction "2_2") (pintype "passive"))
      (node (ref "C604") (pin "2") (pinfunction "2_2") (pintype "passive"))
      (node (ref "C605") (pin "2") (pinfunction "2_2") (pintype "passive"))
      (node (ref "C606") (pin "2") (pinfunction "2_2") (pintype "passive"))
      (node (ref "C607") (pin "2") (pinfunction "2_2") (pintype "passive"))
      (node (ref "C61") (pin "2") (pinfunction "2_2") (pintype "passive"))
      (node (ref "C62") (pin "2") (pinfunction "2_2") (pintype "passive"))
      (node (ref "C63") (pin "2") (pinfunction "2_2") (pintype "passive"))
      (node (ref "C64") (pin "2") (pinfunction "2_2") (pintype "passive"))
      (node (ref "C65") (pin "2") (pinfunction "2_2") (pintype "passive"))
      (node (ref "C66") (pin "2") (pinfunction "2_2") (pintype "passive"))
      (node (ref "C67") (pin "2") (pinfunction "2_2") (pintype "passive"))
      (node (ref "C68") (pin "2") (pinfunction "2_2") (pintype "passive"))
      (node (ref "C69") (pin "2") (pinfunction "2_2") (pintype "passive"))
      (node (ref "C70") (pin "2") (pinfunction "2_2") (pintype "passive"))
      (node (ref "C71") (pin "2") (pinfunction "2_2") (pintype "passive"))
      (node (ref "C72") (pin "2") (pinfunction "2_2") (pintype "passive"))
      (node (ref "C73") (pin "2") (pinfunction "2_2") (pintype "passive"))
      (node (ref "C74") (pin "2") (pinfunction "2_2") (pintype "passive"))
      (node (ref "C75") (pin "2") (pinfunction "2_2") (pintype "passive"))
      (node (ref "C76") (pin "2") (pinfunction "2_2") (pintype "passive"))
      (node (ref "C77") (pin "2") (pinfunction "2_2") (pintype "passive"))
      (node (ref "C78") (pin "2") (pinfunction "2_2") (pintype "passive"))
      (node (ref "C79") (pin "2") (pinfunction "2_2") (pintype "passive"))
      (node (ref "C80") (pin "2") (pinfunction "2_2") (pintype "passive"))
      (node (ref "C81") (pin "2") (pinfunction "2_2") (pintype "passive"))
      (node (ref "C82") (pin "2") (pinfunction "2_2") (pintype "passive"))
      (node (ref "C83") (pin "2") (pinfunction "2_2") (pintype "passive"))
      (node (ref "C84") (pin "2") (pinfunction "2_2") (pintype "passive"))
      (node (ref "C85") (pin "2") (pinfunction "2_2") (pintype "passive"))
      (node (ref "C86") (pin "2") (pinfunction "2_2") (pintype "passive"))
      (node (ref "C87") (pin "2") (pinfunction "2_2") (pintype "passive"))
      (node (ref "C88") (pin "2") (pinfunction "2_2") (pintype "passive"))
      (node (ref "C89") (pin "2") (pinfunction "2_2") (pintype "passive"))
      (node (ref "C90") (pin "2") (pinfunction "2_2") (pintype "passive"))
      (node (ref "C91") (pin "2") (pinfunction "2_2") (pintype "passive"))
      (node (ref "C92") (pin "2") (pinfunction "2_2") (pintype "passive"))
      (node (ref "C93") (pin "2") (pinfunction "2_2") (pintype "passive"))
      (node (ref "C94") (pin "2") (pinfunction "2_2") (pintype "passive"))
      (node (ref "C95") (pin "2") (pinfunction "2_2") (pintype "passive"))
      (node (ref "C96") (pin "2") (pinfunction "2_2") (pintype "passive"))
      (node (ref "C97") (pin "2") (pinfunction "2_2") (pintype "passive"))
      (node (ref "C98") (pin "2") (pinfunction "2_2") (pintype "passive"))
      (node (ref "C99") (pin "2") (pinfunction "2_2") (pintype "passive"))
      (node (ref "R135") (pin "1") (pintype "passive"))
    )
    (net (code "2") (name "/VCC_FPGA1_BATT") (class "Default")
      (node (ref "C118") (pin "1") (pinfunction "1_1") (pintype "passive"))
      (node (ref "D3") (pin "K13") (pinfunction "VCCBATT_0_K13") (pintype "power_in"))
      (node (ref "R134") (pin "1") (pintype "passive"))
      (node (ref "R135") (pin "2") (pintype "passive"))
    )
    (net (code "3") (name "VCC1V0") (class "Default")
      (node (ref "C100") (pin "1") (pinfunction "1_1") (pintype "passive"))
      (node (ref "C108") (pin "1") (pinfunction "1_1") (pintype "passive"))
      (node (ref "C110") (pin "1") (pinfunction "1_1") (pintype "passive"))
      (node (ref "C111") (pin "1") (pinfunction "1_1") (pintype "passive"))
      (node (ref "C112") (pin "1") (pinfunction "1_1") (pintype "passive"))
      (node (ref "C114") (pin "1") (pinfunction "1_1") (pintype "passive"))
      (node (ref "C115") (pin "1") (pinfunction "1_1") (pintype "passive"))
      (node (ref "C116") (pin "1") (pinfunction "1_1") (pintype "passive"))
      (node (ref "C119") (pin "1") (pinfunction "1_1") (pintype "passive"))
      (node (ref "C120") (pin "1") (pinfunction "1_1") (pintype "passive"))
      (node (ref "C121") (pin "1") (pinfunction "1_1") (pintype "passive"))
      (node (ref "C122") (pin "1") (pinfunction "1_1") (pintype "passive"))
      (node (ref "C123") (pin "1") (pinfunction "1_1") (pintype "passive"))
      (node (ref "C540") (pin "1") (pinfunction "1_1") (pintype "passive"))
      (node (ref "C541") (pin "1") (pinfunction "1_1") (pintype "passive"))
      (node (ref "C542") (pin "1") (pinfunction "1_1") (pintype "passive"))
      (node (ref "C543") (pin "1") (pinfunction "1_1") (pintype "passive"))
      (node (ref "C544") (pin "1") (pinfunction "1_1") (pintype "passive"))
      (node (ref "C545") (pin "1") (pinfunction "1_1") (pintype "passive"))
      (node (ref "C546") (pin "1") (pinfunction "1_1") (pintype "passive"))
      (node (ref "C547") (pin "1") (pinfunction "1_1") (pintype "passive"))
      (node (ref "C548") (pin "1") (pinfunction "1_1") (pintype "passive"))
      (node (ref "C555") (pin "1") (pinfunction "1_1") (pintype "passive"))
      (node (ref "C556") (pin "1") (pinfunction "1_1") (pintype "passive"))
      (node (ref "C557") (pin "1") (pinfunction "1_1") (pintype "passive"))
      (node (ref "C558") (pin "1") (pinfunction "1_1") (pintype "passive"))
      (node (ref "C604") (pin "1") (pinfunction "1_1") (pintype "passive"))
      (node (ref "C605") (pin "1") (pinfunction "1_1") (pintype "passive"))
      (node (ref "C606") (pin "1") (pinfunction "1_1") (pintype "passive"))
      (node (ref "C607") (pin "1") (pinfunction "1_1") (pintype "passive"))
      (node (ref "C96") (pin "1") (pinfunction "1_1") (pintype "passive"))
      (node (ref "C97") (pin "1") (pinfunction "1_1") (pintype "passive"))
      (node (ref "C98") (pin "1") (pinfunction "1_1") (pintype "passive"))
      (node (ref "C99") (pin "1") (pinfunction "1_1") (pintype "passive"))
      (node (ref "D3") (pin "AA15") (pinfunction "VCCINT_AA15") (pintype "power_in"))
      (node (ref "D3") (pin "AA17") (pinfunction "VCCINT_AA17") (pintype "power_in"))
      (node (ref "D3") (pin "AA19") (pinfunction "VCCINT_AA19") (pintype "power_in"))
      (node (ref "D3") (pin "AA21") (pinfunction "VCCBRAM_AA21") (pintype "power_in"))
      (node (ref "D3") (pin "AB14") (pinfunction "VCCINT_AB14") (pintype "power_in"))
      (node (ref "D3") (pin "AB16") (pinfunction "VCCINT_AB16") (pintype "power_in"))
      (node (ref "D3") (pin "AB18") (pinfunction "VCCINT_AB18") (pintype "power_in"))
      (node (ref "D3") (pin "AB20") (pinfunction "VCCBRAM_AB20") (pintype "power_in"))
      (node (ref "D3") (pin "AC15") (pinfunction "VCCINT_AC15") (pintype "power_in"))
      (node (ref "D3") (pin "AC17") (pinfunction "VCCINT_AC17") (pintype "power_in"))
      (node (ref "D3") (pin "AC19") (pinfunction "VCCINT_AC19") (pintype "power_in"))
      (node (ref "D3") (pin "AC21") (pinfunction "VCCBRAM_AC21") (pintype "power_in"))
      (node (ref "D3") (pin "AD14") (pinfunction "VCCINT_AD14") (pintype "power_in"))
      (node (ref "D3") (pin "AD16") (pinfunction "VCCINT_AD16") (pintype "power_in"))
      (node (ref "D3") (pin "AD18") (pinfunction "VCCINT_AD18") (pintype "power_in"))
      (node (ref "D3") (pin "AD20") (pinfunction "VCCINT_AD20") (pintype "power_in"))
      (node (ref "D3") (pin "AD22") (pinfunction "VCCINT_AD22") (pintype "power_in"))
      (node (ref "D3") (pin "AE15") (pinfunction "VCCINT_AE15") (pintype "power_in"))
      (node (ref "D3") (pin "AE17") (pinfunction "VCCINT_AE17") (pintype "power_in"))
      (node (ref "D3") (pin "AE19") (pinfunction "VCCINT_AE19") (pintype "power_in"))
      (node (ref "D3") (pin "AE21") (pinfunction "VCCINT_AE21") (pintype "power_in"))
      (node (ref "D3") (pin "K14") (pinfunction "VCCINT_K14") (pintype "power_in"))
      (node (ref "D3") (pin "K16") (pinfunction "VCCINT_K16") (pintype "power_in"))
      (node (ref "D3") (pin "K18") (pinfunction "VCCINT_K18") (pintype "power_in"))
      (node (ref "D3") (pin "K20") (pinfunction "VCCINT_K20") (pintype "power_in"))
      (node (ref "D3") (pin "L15") (pinfunction "VCCINT_L15") (pintype "power_in"))
      (node (ref "D3") (pin "L17") (pinfunction "VCCINT_L17") (pintype "power_in"))
      (node (ref "D3") (pin "L19") (pinfunction "VCCINT_L19") (pintype "power_in"))
      (node (ref "D3") (pin "L21") (pinfunction "VCCINT_L21") (pintype "power_in"))
      (node (ref "D3") (pin "M14") (pinfunction "VCCINT_M14") (pintype "power_in"))
      (node (ref "D3") (pin "M16") (pinfunction "VCCINT_M16") (pintype "power_in"))
      (node (ref "D3") (pin "M18") (pinfunction "VCCINT_M18") (pintype "power_in"))
      (node (ref "D3") (pin "M20") (pinfunction "VCCBRAM_M20") (pintype "power_in"))
      (node (ref "D3") (pin "N15") (pinfunction "VCCINT_N15") (pintype "power_in"))
      (node (ref "D3") (pin "N17") (pinfunction "VCCINT_N17") (pintype "power_in"))
      (node (ref "D3") (pin "N19") (pinfunction "VCCINT_N19") (pintype "power_in"))
      (node (ref "D3") (pin "N21") (pinfunction "VCCBRAM_N21") (pintype "power_in"))
      (node (ref "D3") (pin "P14") (pinfunction "VCCINT_P14") (pintype "power_in"))
      (node (ref "D3") (pin "P16") (pinfunction "VCCINT_P16") (pintype "power_in"))
      (node (ref "D3") (pin "P18") (pinfunction "VCCINT_P18") (pintype "power_in"))
      (node (ref "D3") (pin "P20") (pinfunction "VCCBRAM_P20") (pintype "power_in"))
      (node (ref "D3") (pin "R15") (pinfunction "VCCINT_R15") (pintype "power_in"))
      (node (ref "D3") (pin "R17") (pinfunction "VCCINT_R17") (pintype "power_in"))
      (node (ref "D3") (pin "R19") (pinfunction "VCCINT_R19") (pintype "power_in"))
      (node (ref "D3") (pin "R21") (pinfunction "VCCBRAM_R21") (pintype "power_in"))
      (node (ref "D3") (pin "T14") (pinfunction "VCCINT_T14") (pintype "power_in"))
      (node (ref "D3") (pin "T16") (pinfunction "VCCINT_T16") (pintype "power_in"))
      (node (ref "D3") (pin "T20") (pinfunction "VCCBRAM_T20") (pintype "power_in"))
      (node (ref "D3") (pin "U15") (pinfunction "VCCINT_U15") (pintype "power_in"))
      (node (ref "D3") (pin "U19") (pinfunction "VCCINT_U19") (pintype "power_in"))
      (node (ref "D3") (pin "U21") (pinfunction "VCCBRAM_U21") (pintype "power_in"))
      (node (ref "D3") (pin "V14") (pinfunction "VCCINT_V14") (pintype "power_in"))
      (node (ref "D3") (pin "V16") (pinfunction "VCCINT_V16") (pintype "power_in"))
      (node (ref "D3") (pin "V20") (pinfunction "VCCBRAM_V20") (pintype "power_in"))
      (node (ref "D3") (pin "W15") (pinfunction "VCCINT_W15") (pintype "power_in"))
      (node (ref "D3") (pin "W19") (pinfunction "VCCINT_W19") (pintype "power_in"))
      (node (ref "D3") (pin "W21") (pinfunction "VCCBRAM_W21") (pintype "power_in"))
      (node (ref "D3") (pin "Y14") (pinfunction "VCCINT_Y14") (pintype "power_in"))
      (node (ref "D3") (pin "Y16") (pinfunction "VCCINT_Y16") (pintype "power_in"))
      (node (ref "D3") (pin "Y18") (pinfunction "VCCINT_Y18") (pintype "power_in"))
      (node (ref "D3") (pin "Y20") (pinfunction "VCCBRAM_Y20") (pintype "power_in"))
    )
    (net (code "4") (name "VCC1V8") (class "Default")
      (node (ref "C101") (pin "1") (pinfunction "1_1") (pintype "passive"))
      (node (ref "C102") (pin "1") (pinfunction "1_1") (pintype "passive"))
      (node (ref "C103") (pin "1") (pinfunction "1_1") (pintype "passive"))
      (node (ref "C104") (pin "1") (pinfunction "1_1") (pintype "passive"))
      (node (ref "C105") (pin "1") (pinfunction "1_1") (pintype "passive"))
      (node (ref "C106") (pin "1") (pinfunction "1_1") (pintype "passive"))
      (node (ref "C107") (pin "1") (pinfunction "1_1") (pintype "passive"))
      (node (ref "C549") (pin "1") (pinfunction "1_1") (pintype "passive"))
      (node (ref "C550") (pin "1") (pinfunction "1_1") (pintype "passive"))
      (node (ref "C551") (pin "1") (pinfunction "1_1") (pintype "passive"))
      (node (ref "C552") (pin "1") (pinfunction "1_1") (pintype "passive"))
      (node (ref "C553") (pin "1") (pinfunction "1_1") (pintype "passive"))
      (node (ref "C554") (pin "1") (pinfunction "1_1") (pintype "passive"))
      (node (ref "D3") (pin "AA13") (pinfunction "VCCAUX_AA13") (pintype "power_in"))
      (node (ref "D3") (pin "AA23") (pinfunction "VCCAUX_AA23") (pintype "power_in"))
      (node (ref "D3") (pin "AB12") (pinfunction "VCCAUX_AB12") (pintype "power_in"))
      (node (ref "D3") (pin "AB22") (pinfunction "VCCAUX_AB22") (pintype "power_in"))
      (node (ref "D3") (pin "AC13") (pinfunction "VCCAUX_AC13") (pintype "power_in"))
      (node (ref "D3") (pin "AC23") (pinfunction "VCCAUX_AC23") (pintype "power_in"))
      (node (ref "D3") (pin "AD12") (pinfunction "VCCAUX_AD12") (pintype "power_in"))
      (node (ref "D3") (pin "M22") (pinfunction "VCCAUX_M22") (pintype "power_in"))
      (node (ref "D3") (pin "N13") (pinfunction "VCCAUX_N13") (pintype "power_in"))
      (node (ref "D3") (pin "N23") (pinfunction "VCCAUX_N23") (pintype "power_in"))
      (node (ref "D3") (pin "P12") (pinfunction "VCCAUX_P12") (pintype "power_in"))
      (node (ref "D3") (pin "P22") (pinfunction "VCCAUX_P22") (pintype "power_in"))
      (node (ref "D3") (pin "R13") (pinfunction "VCCAUX_R13") (pintype "power_in"))
      (node (ref "D3") (pin "R23") (pinfunction "VCCAUX_R23") (pintype "power_in"))
      (node (ref "D3") (pin "T12") (pinfunction "VCCAUX_T12") (pintype "power_in"))
      (node (ref "D3") (pin "T22") (pinfunction "VCCAUX_T22") (pintype "power_in"))
      (node (ref "D3") (pin "U13") (pinfunction "VCCAUX_U13") (pintype "power_in"))
      (node (ref "D3") (pin "U23") (pinfunction "VCCAUX_U23") (pintype "power_in"))
      (node (ref "D3") (pin "V12") (pinfunction "VCCAUX_V12") (pintype "power_in"))
      (node (ref "D3") (pin "V22") (pinfunction "VCCAUX_V22") (pintype "power_in"))
      (node (ref "D3") (pin "W13") (pinfunction "VCCAUX_W13") (pintype "power_in"))
      (node (ref "D3") (pin "W23") (pinfunction "VCCAUX_W23") (pintype "power_in"))
      (node (ref "D3") (pin "Y12") (pinfunction "VCCAUX_Y12") (pintype "power_in"))
      (node (ref "D3") (pin "Y22") (pinfunction "VCCAUX_Y22") (pintype "power_in"))
      (node (ref "R134") (pin "2") (pintype "passive"))
    )
    (net (code "5") (name "VCC3V3") (class "Default")
      (node (ref "C36") (pin "1") (pinfunction "1_1") (pintype "passive"))
      (node (ref "C37") (pin "1") (pinfunction "1_1") (pintype "passive"))
      (node (ref "C38") (pin "1") (pinfunction "1_1") (pintype "passive"))
      (node (ref "C39") (pin "1") (pinfunction "1_1") (pintype "passive"))
      (node (ref "C40") (pin "1") (pinfunction "1_1") (pintype "passive"))
      (node (ref "C41") (pin "1") (pinfunction "1_1") (pintype "passive"))
      (node (ref "C42") (pin "1") (pinfunction "1_1") (pintype "passive"))
      (node (ref "C43") (pin "1") (pinfunction "1_1") (pintype "passive"))
      (node (ref "C44") (pin "1") (pinfunction "1_1") (pintype "passive"))
      (node (ref "C45") (pin "1") (pinfunction "1_1") (pintype "passive"))
      (node (ref "C46") (pin "1") (pinfunction "1_1") (pintype "passive"))
      (node (ref "C47") (pin "1") (pinfunction "1_1") (pintype "passive"))
      (node (ref "C48") (pin "1") (pinfunction "1_1") (pintype "passive"))
      (node (ref "C49") (pin "1") (pinfunction "1_1") (pintype "passive"))
      (node (ref "C50") (pin "1") (pinfunction "1_1") (pintype "passive"))
      (node (ref "C51") (pin "1") (pinfunction "1_1") (pintype "passive"))
      (node (ref "C52") (pin "1") (pinfunction "1_1") (pintype "passive"))
      (node (ref "C53") (pin "1") (pinfunction "1_1") (pintype "passive"))
      (node (ref "C538") (pin "1") (pinfunction "1_1") (pintype "passive"))
      (node (ref "C539") (pin "1") (pinfunction "1_1") (pintype "passive"))
      (node (ref "C54") (pin "1") (pinfunction "1_1") (pintype "passive"))
      (node (ref "C55") (pin "1") (pinfunction "1_1") (pintype "passive"))
      (node (ref "C559") (pin "1") (pinfunction "1_1") (pintype "passive"))
      (node (ref "C56") (pin "1") (pinfunction "1_1") (pintype "passive"))
      (node (ref "C57") (pin "1") (pinfunction "1_1") (pintype "passive"))
      (node (ref "C58") (pin "1") (pinfunction "1_1") (pintype "passive"))
      (node (ref "C59") (pin "1") (pinfunction "1_1") (pintype "passive"))
      (node (ref "C60") (pin "1") (pinfunction "1_1") (pintype "passive"))
      (node (ref "C61") (pin "1") (pinfunction "1_1") (pintype "passive"))
      (node (ref "C62") (pin "1") (pinfunction "1_1") (pintype "passive"))
      (node (ref "C63") (pin "1") (pinfunction "1_1") (pintype "passive"))
      (node (ref "C64") (pin "1") (pinfunction "1_1") (pintype "passive"))
      (node (ref "C65") (pin "1") (pinfunction "1_1") (pintype "passive"))
      (node (ref "C66") (pin "1") (pinfunction "1_1") (pintype "passive"))
      (node (ref "C67") (pin "1") (pinfunction "1_1") (pintype "passive"))
      (node (ref "C68") (pin "1") (pinfunction "1_1") (pintype "passive"))
      (node (ref "C69") (pin "1") (pinfunction "1_1") (pintype "passive"))
      (node (ref "C70") (pin "1") (pinfunction "1_1") (pintype "passive"))
      (node (ref "C71") (pin "1") (pinfunction "1_1") (pintype "passive"))
      (node (ref "C72") (pin "1") (pinfunction "1_1") (pintype "passive"))
      (node (ref "C73") (pin "1") (pinfunction "1_1") (pintype "passive"))
      (node (ref "C74") (pin "1") (pinfunction "1_1") (pintype "passive"))
      (node (ref "C75") (pin "1") (pinfunction "1_1") (pintype "passive"))
      (node (ref "C76") (pin "1") (pinfunction "1_1") (pintype "passive"))
      (node (ref "C77") (pin "1") (pinfunction "1_1") (pintype "passive"))
      (node (ref "C78") (pin "1") (pinfunction "1_1") (pintype "passive"))
      (node (ref "C79") (pin "1") (pinfunction "1_1") (pintype "passive"))
      (node (ref "C80") (pin "1") (pinfunction "1_1") (pintype "passive"))
      (node (ref "C81") (pin "1") (pinfunction "1_1") (pintype "passive"))
      (node (ref "C82") (pin "1") (pinfunction "1_1") (pintype "passive"))
      (node (ref "C83") (pin "1") (pinfunction "1_1") (pintype "passive"))
      (node (ref "C84") (pin "1") (pinfunction "1_1") (pintype "passive"))
      (node (ref "C85") (pin "1") (pinfunction "1_1") (pintype "passive"))
      (node (ref "C86") (pin "1") (pinfunction "1_1") (pintype "passive"))
      (node (ref "C87") (pin "1") (pinfunction "1_1") (pintype "passive"))
      (node (ref "C88") (pin "1") (pinfunction "1_1") (pintype "passive"))
      (node (ref "C89") (pin "1") (pinfunction "1_1") (pintype "passive"))
      (node (ref "C90") (pin "1") (pinfunction "1_1") (pintype "passive"))
      (node (ref "C91") (pin "1") (pinfunction "1_1") (pintype "passive"))
      (node (ref "C92") (pin "1") (pinfunction "1_1") (pintype "passive"))
      (node (ref "C93") (pin "1") (pinfunction "1_1") (pintype "passive"))
      (node (ref "C94") (pin "1") (pinfunction "1_1") (pintype "passive"))
      (node (ref "C95") (pin "1") (pinfunction "1_1") (pintype "passive"))
      (node (ref "D3") (pin "A31") (pinfunction "VCCO_17_A31") (pintype "power_in"))
      (node (ref "D3") (pin "A6") (pinfunction "VCCO_37_A6") (pintype "power_in"))
      (node (ref "D3") (pin "AA31") (pinfunction "VCCO_14_AA31") (pintype "power_in"))
      (node (ref "D3") (pin "AA6") (pinfunction "VCCO_34_AA6") (pintype "power_in"))
      (node (ref "D3") (pin "AB28") (pinfunction "VCCO_14_AB28") (pintype "power_in"))
      (node (ref "D3") (pin "AB3") (pinfunction "VCCO_34_AB3") (pintype "power_in"))
      (node (ref "D3") (pin "AC10") (pinfunction "VCCO_34_AC10") (pintype "power_in"))
      (node (ref "D3") (pin "AC25") (pinfunction "VCCO_13_AC25") (pintype "power_in"))
      (node (ref "D3") (pin "AD32") (pinfunction "VCCO_13_AD32") (pintype "power_in"))
      (node (ref "D3") (pin "AD7") (pinfunction "VCCO_33_AD7") (pintype "power_in"))
      (node (ref "D3") (pin "AE29") (pinfunction "VCCO_13_AE29") (pintype "power_in"))
      (node (ref "D3") (pin "AE4") (pinfunction "VCCO_33_AE4") (pintype "power_in"))
      (node (ref "D3") (pin "AF1") (pinfunction "VCCO_33_AF1") (pintype "power_in"))
      (node (ref "D3") (pin "AF11") (pinfunction "VCCO_33_AF11") (pintype "power_in"))
      (node (ref "D3") (pin "AF26") (pinfunction "VCCO_13_AF26") (pintype "power_in"))
      (node (ref "D3") (pin "AG33") (pinfunction "VCCO_13_AG33") (pintype "power_in"))
      (node (ref "D3") (pin "AG8") (pinfunction "VCCO_33_AG8") (pintype "power_in"))
      (node (ref "D3") (pin "AH30") (pinfunction "VCCO_13_AH30") (pintype "power_in"))
      (node (ref "D3") (pin "AH5") (pinfunction "VCCO_33_AH5") (pintype "power_in"))
      (node (ref "D3") (pin "AJ2") (pinfunction "VCCO_32_AJ2") (pintype "power_in"))
      (node (ref "D3") (pin "AJ27") (pinfunction "VCCO_12_AJ27") (pintype "power_in"))
      (node (ref "D3") (pin "AK34") (pinfunction "VCCO_12_AK34") (pintype "power_in"))
      (node (ref "D3") (pin "AK9") (pinfunction "VCCO_32_AK9") (pintype "power_in"))
      (node (ref "D3") (pin "AL31") (pinfunction "VCCO_12_AL31") (pintype "power_in"))
      (node (ref "D3") (pin "AL6") (pinfunction "VCCO_32_AL6") (pintype "power_in"))
      (node (ref "D3") (pin "AM28") (pinfunction "VCCO_12_AM28") (pintype "power_in"))
      (node (ref "D3") (pin "AM3") (pinfunction "VCCO_32_AM3") (pintype "power_in"))
      (node (ref "D3") (pin "AN10") (pinfunction "VCCO_32_AN10") (pintype "power_in"))
      (node (ref "D3") (pin "AN25") (pinfunction "VCCO_12_AN25") (pintype "power_in"))
      (node (ref "D3") (pin "AP32") (pinfunction "VCCO_12_AP32") (pintype "power_in"))
      (node (ref "D3") (pin "AP7") (pinfunction "VCCO_32_AP7") (pintype "power_in"))
      (node (ref "D3") (pin "B28") (pinfunction "VCCO_17_B28") (pintype "power_in"))
      (node (ref "D3") (pin "B3") (pinfunction "VCCO_37_B3") (pintype "power_in"))
      (node (ref "D3") (pin "C10") (pinfunction "VCCO_37_C10") (pintype "power_in"))
      (node (ref "D3") (pin "C25") (pinfunction "VCCO_17_C25") (pintype "power_in"))
      (node (ref "D3") (pin "D32") (pinfunction "VCCO_17_D32") (pintype "power_in"))
      (node (ref "D3") (pin "D7") (pinfunction "VCCO_37_D7") (pintype "power_in"))
      (node (ref "D3") (pin "E29") (pinfunction "VCCO_17_E29") (pintype "power_in"))
      (node (ref "D3") (pin "E4") (pinfunction "VCCO_37_E4") (pintype "power_in"))
      (node (ref "D3") (pin "F1") (pinfunction "VCCO_36_F1") (pintype "power_in"))
      (node (ref "D3") (pin "F11") (pinfunction "VCCO_37_F11") (pintype "power_in"))
      (node (ref "D3") (pin "F26") (pinfunction "VCCO_17_F26") (pintype "power_in"))
      (node (ref "D3") (pin "G33") (pinfunction "VCCO_16_G33") (pintype "power_in"))
      (node (ref "D3") (pin "G8") (pinfunction "VCCO_36_G8") (pintype "power_in"))
      (node (ref "D3") (pin "H30") (pinfunction "VCCO_16_H30") (pintype "power_in"))
      (node (ref "D3") (pin "H5") (pinfunction "VCCO_36_H5") (pintype "power_in"))
      (node (ref "D3") (pin "J12") (pinfunction "VCCO_36_J12") (pintype "power_in"))
      (node (ref "D3") (pin "J2") (pinfunction "VCCO_36_J2") (pintype "power_in"))
      (node (ref "D3") (pin "J27") (pinfunction "VCCO_16_J27") (pintype "power_in"))
      (node (ref "D3") (pin "K24") (pinfunction "VCCO_16_K24") (pintype "power_in"))
      (node (ref "D3") (pin "K34") (pinfunction "VCCO_16_K34") (pintype "power_in"))
      (node (ref "D3") (pin "K9") (pinfunction "VCCO_36_K9") (pintype "power_in"))
      (node (ref "D3") (pin "L13") (pinfunction "VCCO_0_L13") (pintype "power_in"))
      (node (ref "D3") (pin "L31") (pinfunction "VCCO_16_L31") (pintype "power_in"))
      (node (ref "D3") (pin "L6") (pinfunction "VCCO_36_L6") (pintype "power_in"))
      (node (ref "D3") (pin "M28") (pinfunction "VCCO_15_M28") (pintype "power_in"))
      (node (ref "D3") (pin "M3") (pinfunction "VCCO_35_M3") (pintype "power_in"))
      (node (ref "D3") (pin "N10") (pinfunction "VCCO_35_N10") (pintype "power_in"))
      (node (ref "D3") (pin "N25") (pinfunction "VCCO_15_N25") (pintype "power_in"))
      (node (ref "D3") (pin "P32") (pinfunction "VCCO_15_P32") (pintype "power_in"))
      (node (ref "D3") (pin "P7") (pinfunction "VCCO_35_P7") (pintype "power_in"))
      (node (ref "D3") (pin "R29") (pinfunction "VCCO_15_R29") (pintype "power_in"))
      (node (ref "D3") (pin "R4") (pinfunction "VCCO_35_R4") (pintype "power_in"))
      (node (ref "D3") (pin "T1") (pinfunction "VCCO_35_T1") (pintype "power_in"))
      (node (ref "D3") (pin "T11") (pinfunction "VCCO_0_T11") (pintype "power_in"))
      (node (ref "D3") (pin "T18") (pinfunction "VCCADC_0_T18") (pintype "power_in"))
      (node (ref "D3") (pin "T26") (pinfunction "VCCO_15_T26") (pintype "power_in"))
      (node (ref "D3") (pin "U33") (pinfunction "VCCO_15_U33") (pintype "power_in"))
      (node (ref "D3") (pin "U8") (pinfunction "VCCO_35_U8") (pintype "power_in"))
      (node (ref "D3") (pin "V30") (pinfunction "VCCO_14_V30") (pintype "power_in"))
      (node (ref "D3") (pin "V5") (pinfunction "VCCO_34_V5") (pintype "power_in"))
      (node (ref "D3") (pin "W2") (pinfunction "VCCO_34_W2") (pintype "power_in"))
      (node (ref "D3") (pin "W27") (pinfunction "VCCO_14_W27") (pintype "power_in"))
      (node (ref "D3") (pin "Y24") (pinfunction "VCCO_14_Y24") (pintype "power_in"))
      (node (ref "D3") (pin "Y34") (pinfunction "VCCO_14_Y34") (pintype "power_in"))
      (node (ref "D3") (pin "Y9") (pinfunction "VCCO_34_Y9") (pintype "power_in"))
    )
  )
)
